# hires-Addon_Build_003.net
KiCad netlist of a schematic drawn in EAGLE
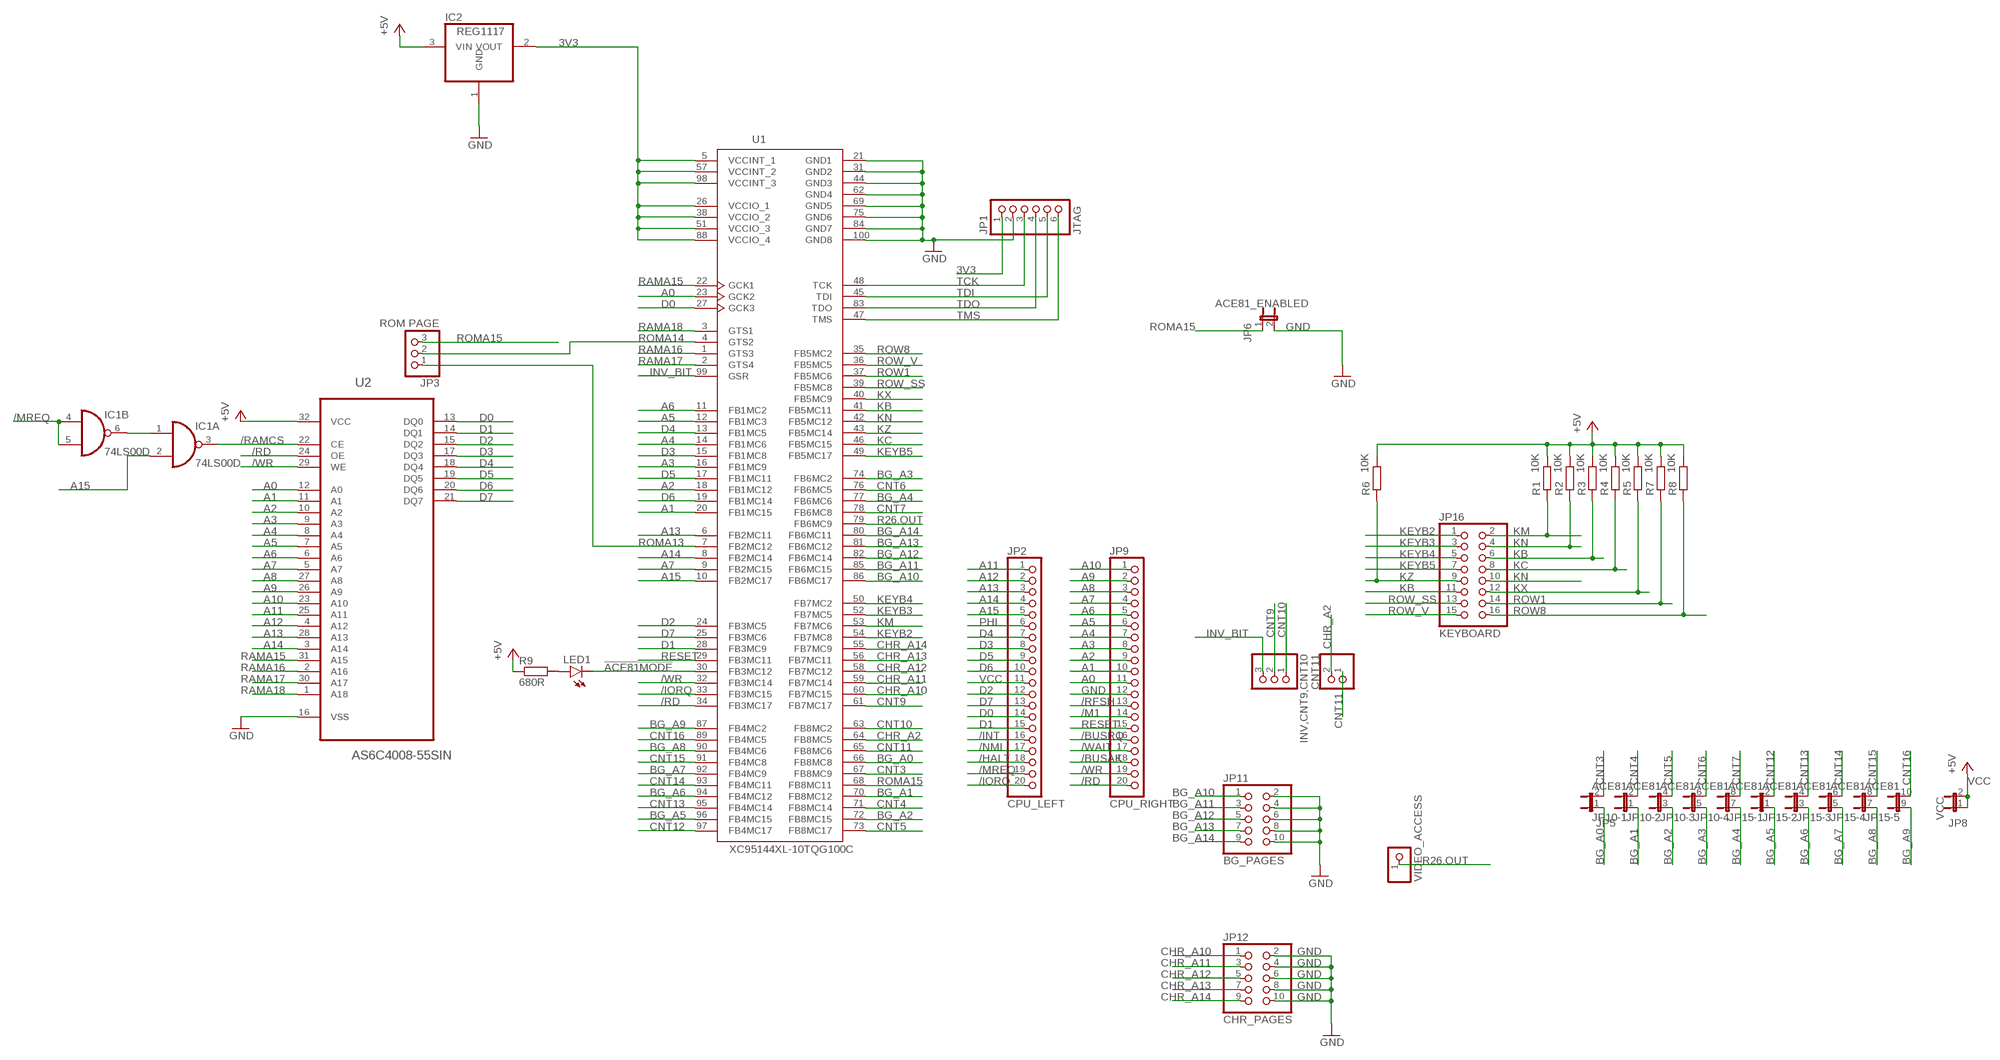
[diagram p0: schematic, sheet 1]

(export (version "E")
  (design (tool "Eeschema 10.0.6"))
  (components
    (comp (ref "CNT11")
      (value "PINHD-1X2")
      (footprint "eagle-import:1X02")
      (libsource (lib "eagle-import") (part "PINHD-1X2"))
    )
    (comp (ref "IC1")
      (value "74LS00D")
      (footprint "eagle-import:SO14")
      (libsource (lib "eagle-import") (part "7400DLS"))
    )
    (comp (ref "IC2")
      (value "REG1117")
      (footprint "eagle-import:SOT223")
      (libsource (lib "eagle-import") (part "REG1117"))
    )
    (comp (ref "INV,CNT9,CNT10")
      (value "PINHD-1X3")
      (footprint "eagle-import:1X03")
      (libsource (lib "eagle-import") (part "pinhead_44166543_PINHD-1X3"))
    )
    (comp (ref "JP1")
      (value "JTAG")
      (footprint "eagle-import:1X06_90")
      (libsource (lib "eagle-import") (part "PINHD-1X6/90"))
    )
    (comp (ref "JP2")
      (value "CPU_LEFT")
      (footprint "eagle-import:1X20")
      (libsource (lib "eagle-import") (part "PINHD-1X20"))
    )
    (comp (ref "JP3")
      (value "ROM PAGE")
      (footprint "eagle-import:1X03")
      (libsource (lib "eagle-import") (part "PINHD-1X3"))
    )
    (comp (ref "JP5")
      (value "JP1E1Q")
      (footprint "eagle-import:JP1Q")
      (libsource (lib "eagle-import") (part "JP1E1Q"))
    )
    (comp (ref "JP6")
      (value "ACE81_ENABLED")
      (footprint "eagle-import:JP1Q")
      (libsource (lib "eagle-import") (part "JP1E1Q"))
    )
    (comp (ref "JP8")
      (value "VCC")
      (footprint "eagle-import:JP1Q")
      (libsource (lib "eagle-import") (part "JP1E1Q"))
    )
    (comp (ref "JP9")
      (value "CPU_RIGHT")
      (footprint "eagle-import:1X20")
      (libsource (lib "eagle-import") (part "PINHD-1X20"))
    )
    (comp (ref "JP10")
      (value "ACE81")
      (footprint "eagle-import:JP4Q")
      (libsource (lib "eagle-import") (part "JP4QE"))
    )
    (comp (ref "JP11")
      (value "BG_PAGES")
      (footprint "eagle-import:2X05")
      (libsource (lib "eagle-import") (part "PINHD-2X5"))
    )
    (comp (ref "JP12")
      (value "CHR_PAGES")
      (footprint "eagle-import:2X05")
      (libsource (lib "eagle-import") (part "PINHD-2X5"))
    )
    (comp (ref "JP14")
      (value "VIDEO_ACCESS")
      (footprint "eagle-import:1X01")
      (libsource (lib "eagle-import") (part "PINHD-1X1"))
    )
    (comp (ref "JP15")
      (value "ACE81")
      (footprint "eagle-import:JP5Q")
      (libsource (lib "eagle-import") (part "JP5QE"))
    )
    (comp (ref "JP16")
      (value "KEYBOARD")
      (footprint "eagle-import:2X08")
      (libsource (lib "eagle-import") (part "PINHD-2X8"))
    )
    (comp (ref "LED1")
      (value "LED3MM")
      (footprint "eagle-import:LED3MM")
      (libsource (lib "eagle-import") (part "LED3MM"))
    )
    (comp (ref "R1")
      (value "10K")
      (footprint "eagle-import:0204_7")
      (libsource (lib "eagle-import") (part "R-EU_0204/7"))
    )
    (comp (ref "R2")
      (value "10K")
      (footprint "eagle-import:0204_7")
      (libsource (lib "eagle-import") (part "R-EU_0204/7"))
    )
    (comp (ref "R3")
      (value "10K")
      (footprint "eagle-import:0204_7")
      (libsource (lib "eagle-import") (part "R-EU_0204/7"))
    )
    (comp (ref "R4")
      (value "10K")
      (footprint "eagle-import:0204_7")
      (libsource (lib "eagle-import") (part "R-EU_0204/7"))
    )
    (comp (ref "R5")
      (value "10K")
      (footprint "eagle-import:0204_7")
      (libsource (lib "eagle-import") (part "R-EU_0204/7"))
    )
    (comp (ref "R6")
      (value "10K")
      (footprint "eagle-import:0204_7")
      (libsource (lib "eagle-import") (part "R-EU_0204/7"))
    )
    (comp (ref "R7")
      (value "10K")
      (footprint "eagle-import:0204_7")
      (libsource (lib "eagle-import") (part "R-EU_0204/7"))
    )
    (comp (ref "R8")
      (value "10K")
      (footprint "eagle-import:0204_7")
      (libsource (lib "eagle-import") (part "R-EU_0204/7"))
    )
    (comp (ref "R9")
      (value "680R")
      (footprint "eagle-import:0204_7")
      (libsource (lib "eagle-import") (part "R-EU_0204/7"))
    )
    (comp (ref "U1")
      (value "XC95144XL-10TQG100C")
      (footprint "eagle-import:TQFP100")
      (fields (field (name "MF") "Xilinx Inc."))
      (libsource (lib "eagle-import") (part "XC95144XL-10TQG100C"))
    )
    (comp (ref "U2")
      (value "AS6C4008-55SIN")
      (footprint "eagle-import:SOIC127P1407X299-32N")
      (fields (field (name "MF") "Alliance"))
      (libsource (lib "eagle-import") (part "AS6C4008-55SIN"))
    )
  )
  (nets
    (net (code "1") (name "+5V") (class "Default")
      (node (ref "IC2") (pin "3") (pinfunction "VIN_3") (pintype "input"))
      (node (ref "JP2") (pin "11") (pinfunction "11_11") (pintype "passive"))
      (node (ref "JP8") (pin "1") (pinfunction "1_1") (pintype "passive"))
      (node (ref "JP8") (pin "2") (pinfunction "2_2") (pintype "passive"))
      (node (ref "R1") (pin "2") (pinfunction "2_2") (pintype "passive"))
      (node (ref "R2") (pin "2") (pinfunction "2_2") (pintype "passive"))
      (node (ref "R3") (pin "2") (pinfunction "2_2") (pintype "passive"))
      (node (ref "R4") (pin "2") (pinfunction "2_2") (pintype "passive"))
      (node (ref "R5") (pin "2") (pinfunction "2_2") (pintype "passive"))
      (node (ref "R6") (pin "2") (pinfunction "2_2") (pintype "passive"))
      (node (ref "R7") (pin "2") (pinfunction "2_2") (pintype "passive"))
      (node (ref "R8") (pin "2") (pinfunction "2_2") (pintype "passive"))
      (node (ref "R9") (pin "1") (pinfunction "1_1") (pintype "passive"))
      (node (ref "U2") (pin "32") (pinfunction "VCC_32") (pintype "power_in"))
    )
    (net (code "2") (name "/3V3") (class "Default")
      (node (ref "IC2") (pin "2") (pinfunction "VOUT_2") (pintype "output"))
      (node (ref "JP1") (pin "1") (pinfunction "1_1") (pintype "passive"))
      (node (ref "U1") (pin "26") (pinfunction "VCCIO_1_26") (pintype "power_in"))
      (node (ref "U1") (pin "38") (pinfunction "VCCIO_2_38") (pintype "power_in"))
      (node (ref "U1") (pin "5") (pinfunction "VCCINT_1_5") (pintype "power_in"))
      (node (ref "U1") (pin "51") (pinfunction "VCCIO_3_51") (pintype "power_in"))
      (node (ref "U1") (pin "57") (pinfunction "VCCINT_2_57") (pintype "power_in"))
      (node (ref "U1") (pin "88") (pinfunction "VCCIO_4_88") (pintype "power_in"))
      (node (ref "U1") (pin "98") (pinfunction "VCCINT_3_98") (pintype "power_in"))
    )
    (net (code "3") (name "/A0") (class "Default")
      (node (ref "JP9") (pin "11") (pinfunction "11_11") (pintype "passive"))
      (node (ref "U1") (pin "23") (pinfunction "GCK2_23") (pintype "bidirectional"))
      (node (ref "U2") (pin "12") (pinfunction "A0_12") (pintype "input"))
    )
    (net (code "4") (name "/A1") (class "Default")
      (node (ref "JP9") (pin "10") (pinfunction "10_10") (pintype "passive"))
      (node (ref "U1") (pin "20") (pinfunction "FB1MC15_20") (pintype "bidirectional"))
      (node (ref "U2") (pin "11") (pinfunction "A1_11") (pintype "input"))
    )
    (net (code "5") (name "/A2") (class "Default")
      (node (ref "JP9") (pin "9") (pinfunction "9_9") (pintype "passive"))
      (node (ref "U1") (pin "18") (pinfunction "FB1MC12_18") (pintype "bidirectional"))
      (node (ref "U2") (pin "10") (pinfunction "A2_10") (pintype "input"))
    )
    (net (code "6") (name "/A3") (class "Default")
      (node (ref "JP9") (pin "8") (pinfunction "8_8") (pintype "passive"))
      (node (ref "U1") (pin "16") (pinfunction "FB1MC9_16") (pintype "bidirectional"))
      (node (ref "U2") (pin "9") (pinfunction "A3_9") (pintype "input"))
    )
    (net (code "7") (name "/A4") (class "Default")
      (node (ref "JP9") (pin "7") (pinfunction "7_7") (pintype "passive"))
      (node (ref "U1") (pin "14") (pinfunction "FB1MC6_14") (pintype "bidirectional"))
      (node (ref "U2") (pin "8") (pinfunction "A4_8") (pintype "input"))
    )
    (net (code "8") (name "/A5") (class "Default")
      (node (ref "JP9") (pin "6") (pinfunction "6_6") (pintype "passive"))
      (node (ref "U1") (pin "12") (pinfunction "FB1MC3_12") (pintype "bidirectional"))
      (node (ref "U2") (pin "7") (pinfunction "A5_7") (pintype "input"))
    )
    (net (code "9") (name "/A6") (class "Default")
      (node (ref "JP9") (pin "5") (pinfunction "5_5") (pintype "passive"))
      (node (ref "U1") (pin "11") (pinfunction "FB1MC2_11") (pintype "bidirectional"))
      (node (ref "U2") (pin "6") (pinfunction "A6_6") (pintype "input"))
    )
    (net (code "10") (name "/A7") (class "Default")
      (node (ref "JP9") (pin "4") (pinfunction "4_4") (pintype "passive"))
      (node (ref "U1") (pin "9") (pinfunction "FB2MC15_9") (pintype "bidirectional"))
      (node (ref "U2") (pin "5") (pinfunction "A7_5") (pintype "input"))
    )
    (net (code "11") (name "/A8") (class "Default")
      (node (ref "JP9") (pin "3") (pinfunction "3_3") (pintype "passive"))
      (node (ref "U2") (pin "27") (pinfunction "A8_27") (pintype "input"))
    )
    (net (code "12") (name "/A9") (class "Default")
      (node (ref "JP9") (pin "2") (pinfunction "2_2") (pintype "passive"))
      (node (ref "U2") (pin "26") (pinfunction "A9_26") (pintype "input"))
    )
    (net (code "13") (name "/A10") (class "Default")
      (node (ref "JP9") (pin "1") (pinfunction "1_1") (pintype "passive"))
      (node (ref "U2") (pin "23") (pinfunction "A10_23") (pintype "input"))
    )
    (net (code "14") (name "/A11") (class "Default")
      (node (ref "JP2") (pin "1") (pinfunction "1_1") (pintype "passive"))
      (node (ref "U2") (pin "25") (pinfunction "A11_25") (pintype "input"))
    )
    (net (code "15") (name "/A12") (class "Default")
      (node (ref "JP2") (pin "2") (pinfunction "2_2") (pintype "passive"))
      (node (ref "U2") (pin "4") (pinfunction "A12_4") (pintype "input"))
    )
    (net (code "16") (name "/A13") (class "Default")
      (node (ref "JP2") (pin "3") (pinfunction "3_3") (pintype "passive"))
      (node (ref "U1") (pin "6") (pinfunction "FB2MC11_6") (pintype "bidirectional"))
      (node (ref "U2") (pin "28") (pinfunction "A13_28") (pintype "input"))
    )
    (net (code "17") (name "/A14") (class "Default")
      (node (ref "JP2") (pin "4") (pinfunction "4_4") (pintype "passive"))
      (node (ref "U1") (pin "8") (pinfunction "FB2MC14_8") (pintype "bidirectional"))
      (node (ref "U2") (pin "3") (pinfunction "A14_3") (pintype "input"))
    )
    (net (code "18") (name "/A15") (class "Default")
      (node (ref "IC1") (pin "2") (pinfunction "I1_2") (pintype "input"))
      (node (ref "JP2") (pin "5") (pinfunction "5_5") (pintype "passive"))
      (node (ref "U1") (pin "10") (pinfunction "FB2MC17_10") (pintype "bidirectional"))
    )
    (net (code "19") (name "/BG_A0") (class "Default")
      (node (ref "JP5") (pin "1") (pinfunction "1_1") (pintype "passive"))
      (node (ref "U1") (pin "66") (pinfunction "FB8MC8_66") (pintype "bidirectional"))
    )
    (net (code "20") (name "/BG_A1") (class "Default")
      (node (ref "JP10") (pin "1") (pinfunction "1_1") (pintype "passive"))
      (node (ref "U1") (pin "70") (pinfunction "FB8MC12_70") (pintype "bidirectional"))
    )
    (net (code "21") (name "/BG_A2") (class "Default")
      (node (ref "JP10") (pin "3") (pinfunction "1_3") (pintype "passive"))
      (node (ref "U1") (pin "72") (pinfunction "FB8MC15_72") (pintype "bidirectional"))
    )
    (net (code "22") (name "/BG_A3") (class "Default")
      (node (ref "JP10") (pin "5") (pinfunction "1_5") (pintype "passive"))
      (node (ref "U1") (pin "74") (pinfunction "FB6MC2_74") (pintype "bidirectional"))
    )
    (net (code "23") (name "/BG_A4") (class "Default")
      (node (ref "JP10") (pin "7") (pinfunction "1_7") (pintype "passive"))
      (node (ref "U1") (pin "77") (pinfunction "FB6MC6_77") (pintype "bidirectional"))
    )
    (net (code "24") (name "/BG_A5") (class "Default")
      (node (ref "JP15") (pin "1") (pinfunction "1_1") (pintype "passive"))
      (node (ref "U1") (pin "96") (pinfunction "FB4MC15_96") (pintype "bidirectional"))
    )
    (net (code "25") (name "/BG_A6") (class "Default")
      (node (ref "JP15") (pin "3") (pinfunction "1_3") (pintype "passive"))
      (node (ref "U1") (pin "94") (pinfunction "FB4MC12_94") (pintype "bidirectional"))
    )
    (net (code "26") (name "/BG_A7") (class "Default")
      (node (ref "JP15") (pin "5") (pinfunction "1_5") (pintype "passive"))
      (node (ref "U1") (pin "92") (pinfunction "FB4MC9_92") (pintype "bidirectional"))
    )
    (net (code "27") (name "/BG_A8") (class "Default")
      (node (ref "JP15") (pin "7") (pinfunction "1_7") (pintype "passive"))
      (node (ref "U1") (pin "90") (pinfunction "FB4MC6_90") (pintype "bidirectional"))
    )
    (net (code "28") (name "/BG_A9") (class "Default")
      (node (ref "JP15") (pin "9") (pinfunction "1_9") (pintype "passive"))
      (node (ref "U1") (pin "87") (pinfunction "FB4MC2_87") (pintype "bidirectional"))
    )
    (net (code "29") (name "/BG_A10") (class "Default")
      (node (ref "JP11") (pin "1") (pinfunction "1_1") (pintype "passive"))
      (node (ref "U1") (pin "86") (pinfunction "FB6MC17_86") (pintype "bidirectional"))
    )
    (net (code "30") (name "/BG_A11") (class "Default")
      (node (ref "JP11") (pin "3") (pinfunction "3_3") (pintype "passive"))
      (node (ref "U1") (pin "85") (pinfunction "FB6MC15_85") (pintype "bidirectional"))
    )
    (net (code "31") (name "/BG_A12") (class "Default")
      (node (ref "JP11") (pin "5") (pinfunction "5_5") (pintype "passive"))
      (node (ref "U1") (pin "82") (pinfunction "FB6MC14_82") (pintype "bidirectional"))
    )
    (net (code "32") (name "/BG_A13") (class "Default")
      (node (ref "JP11") (pin "7") (pinfunction "7_7") (pintype "passive"))
      (node (ref "U1") (pin "81") (pinfunction "FB6MC12_81") (pintype "bidirectional"))
    )
    (net (code "33") (name "/BG_A14") (class "Default")
      (node (ref "JP11") (pin "9") (pinfunction "9_9") (pintype "passive"))
      (node (ref "U1") (pin "80") (pinfunction "FB6MC11_80") (pintype "bidirectional"))
    )
    (net (code "34") (name "/CHR_A2") (class "Default")
      (node (ref "CNT11") (pin "2") (pinfunction "2_2") (pintype "passive"))
      (node (ref "U1") (pin "64") (pinfunction "FB8MC5_64") (pintype "bidirectional"))
    )
    (net (code "35") (name "/CHR_A10") (class "Default")
      (node (ref "JP12") (pin "1") (pinfunction "1_1") (pintype "passive"))
      (node (ref "U1") (pin "60") (pinfunction "FB7MC15_60") (pintype "bidirectional"))
    )
    (net (code "36") (name "/CHR_A11") (class "Default")
      (node (ref "JP12") (pin "3") (pinfunction "3_3") (pintype "passive"))
      (node (ref "U1") (pin "59") (pinfunction "FB7MC14_59") (pintype "bidirectional"))
    )
    (net (code "37") (name "/CHR_A12") (class "Default")
      (node (ref "JP12") (pin "5") (pinfunction "5_5") (pintype "passive"))
      (node (ref "U1") (pin "58") (pinfunction "FB7MC12_58") (pintype "bidirectional"))
    )
    (net (code "38") (name "/CHR_A13") (class "Default")
      (node (ref "JP12") (pin "7") (pinfunction "7_7") (pintype "passive"))
      (node (ref "U1") (pin "56") (pinfunction "FB7MC11_56") (pintype "bidirectional"))
    )
    (net (code "39") (name "/CHR_A14") (class "Default")
      (node (ref "JP12") (pin "9") (pinfunction "9_9") (pintype "passive"))
      (node (ref "U1") (pin "55") (pinfunction "FB7MC9_55") (pintype "bidirectional"))
    )
    (net (code "40") (name "/CNT3") (class "Default")
      (node (ref "JP5") (pin "2") (pinfunction "2_2") (pintype "passive"))
      (node (ref "U1") (pin "67") (pinfunction "FB8MC9_67") (pintype "bidirectional"))
    )
    (net (code "41") (name "/CNT4") (class "Default")
      (node (ref "JP10") (pin "2") (pinfunction "2_2") (pintype "passive"))
      (node (ref "U1") (pin "71") (pinfunction "FB8MC14_71") (pintype "bidirectional"))
    )
    (net (code "42") (name "/CNT5") (class "Default")
      (node (ref "JP10") (pin "4") (pinfunction "2_4") (pintype "passive"))
      (node (ref "U1") (pin "73") (pinfunction "FB8MC17_73") (pintype "bidirectional"))
    )
    (net (code "43") (name "/CNT6") (class "Default")
      (node (ref "JP10") (pin "6") (pinfunction "2_6") (pintype "passive"))
      (node (ref "U1") (pin "76") (pinfunction "FB6MC5_76") (pintype "bidirectional"))
    )
    (net (code "44") (name "/CNT7") (class "Default")
      (node (ref "JP10") (pin "8") (pinfunction "2_8") (pintype "passive"))
      (node (ref "U1") (pin "78") (pinfunction "FB6MC8_78") (pintype "bidirectional"))
    )
    (net (code "45") (name "/CNT9") (class "Default")
      (node (ref "INV,CNT9,CNT10") (pin "2") (pinfunction "2_2") (pintype "passive"))
      (node (ref "U1") (pin "61") (pinfunction "FB7MC17_61") (pintype "bidirectional"))
    )
    (net (code "46") (name "/CNT10") (class "Default")
      (node (ref "INV,CNT9,CNT10") (pin "1") (pinfunction "1_1") (pintype "passive"))
      (node (ref "U1") (pin "63") (pinfunction "FB8MC2_63") (pintype "bidirectional"))
    )
    (net (code "47") (name "/CNT11") (class "Default")
      (node (ref "CNT11") (pin "1") (pinfunction "1_1") (pintype "passive"))
      (node (ref "U1") (pin "65") (pinfunction "FB8MC6_65") (pintype "bidirectional"))
    )
    (net (code "48") (name "/CNT12") (class "Default")
      (node (ref "JP15") (pin "2") (pinfunction "2_2") (pintype "passive"))
      (node (ref "U1") (pin "97") (pinfunction "FB4MC17_97") (pintype "bidirectional"))
    )
    (net (code "49") (name "/CNT13") (class "Default")
      (node (ref "JP15") (pin "4") (pinfunction "2_4") (pintype "passive"))
      (node (ref "U1") (pin "95") (pinfunction "FB4MC14_95") (pintype "bidirectional"))
    )
    (net (code "50") (name "/CNT14") (class "Default")
      (node (ref "JP15") (pin "6") (pinfunction "2_6") (pintype "passive"))
      (node (ref "U1") (pin "93") (pinfunction "FB4MC11_93") (pintype "bidirectional"))
    )
    (net (code "51") (name "/CNT15") (class "Default")
      (node (ref "JP15") (pin "8") (pinfunction "2_8") (pintype "passive"))
      (node (ref "U1") (pin "91") (pinfunction "FB4MC8_91") (pintype "bidirectional"))
    )
    (net (code "52") (name "/CNT16") (class "Default")
      (node (ref "JP15") (pin "10") (pinfunction "2_10") (pintype "passive"))
      (node (ref "U1") (pin "89") (pinfunction "FB4MC5_89") (pintype "bidirectional"))
    )
    (net (code "53") (name "/D0") (class "Default")
      (node (ref "JP2") (pin "14") (pinfunction "14_14") (pintype "passive"))
      (node (ref "U1") (pin "27") (pinfunction "GCK3_27") (pintype "bidirectional"))
      (node (ref "U2") (pin "13") (pinfunction "DQ0_13") (pintype "output"))
    )
    (net (code "54") (name "/D1") (class "Default")
      (node (ref "JP2") (pin "15") (pinfunction "15_15") (pintype "passive"))
      (node (ref "U1") (pin "28") (pinfunction "FB3MC9_28") (pintype "bidirectional"))
      (node (ref "U2") (pin "14") (pinfunction "DQ1_14") (pintype "output"))
    )
    (net (code "55") (name "/D2") (class "Default")
      (node (ref "JP2") (pin "12") (pinfunction "12_12") (pintype "passive"))
      (node (ref "U1") (pin "24") (pinfunction "FB3MC5_24") (pintype "bidirectional"))
      (node (ref "U2") (pin "15") (pinfunction "DQ2_15") (pintype "output"))
    )
    (net (code "56") (name "/D3") (class "Default")
      (node (ref "JP2") (pin "8") (pinfunction "8_8") (pintype "passive"))
      (node (ref "U1") (pin "15") (pinfunction "FB1MC8_15") (pintype "bidirectional"))
      (node (ref "U2") (pin "17") (pinfunction "DQ3_17") (pintype "output"))
    )
    (net (code "57") (name "/D4") (class "Default")
      (node (ref "JP2") (pin "7") (pinfunction "7_7") (pintype "passive"))
      (node (ref "U1") (pin "13") (pinfunction "FB1MC5_13") (pintype "bidirectional"))
      (node (ref "U2") (pin "18") (pinfunction "DQ4_18") (pintype "output"))
    )
    (net (code "58") (name "/D5") (class "Default")
      (node (ref "JP2") (pin "9") (pinfunction "9_9") (pintype "passive"))
      (node (ref "U1") (pin "17") (pinfunction "FB1MC11_17") (pintype "bidirectional"))
      (node (ref "U2") (pin "19") (pinfunction "DQ5_19") (pintype "output"))
    )
    (net (code "59") (name "/D6") (class "Default")
      (node (ref "JP2") (pin "10") (pinfunction "10_10") (pintype "passive"))
      (node (ref "U1") (pin "19") (pinfunction "FB1MC14_19") (pintype "bidirectional"))
      (node (ref "U2") (pin "20") (pinfunction "DQ6_20") (pintype "output"))
    )
    (net (code "60") (name "/D7") (class "Default")
      (node (ref "JP2") (pin "13") (pinfunction "13_13") (pintype "passive"))
      (node (ref "U1") (pin "25") (pinfunction "FB3MC6_25") (pintype "bidirectional"))
      (node (ref "U2") (pin "21") (pinfunction "DQ7_21") (pintype "output"))
    )
    (net (code "61") (name "/INV_BIT") (class "Default")
      (node (ref "INV,CNT9,CNT10") (pin "3") (pinfunction "3_3") (pintype "passive"))
      (node (ref "U1") (pin "99") (pinfunction "GSR_99") (pintype "bidirectional"))
    )
    (net (code "62") (name "/KB") (class "Default")
      (node (ref "JP16") (pin "11") (pinfunction "11_11") (pintype "passive"))
      (node (ref "JP16") (pin "6") (pinfunction "6_6") (pintype "passive"))
      (node (ref "R3") (pin "1") (pinfunction "1_1") (pintype "passive"))
      (node (ref "U1") (pin "41") (pinfunction "FB5MC11_41") (pintype "bidirectional"))
    )
    (net (code "63") (name "/KC") (class "Default")
      (node (ref "JP16") (pin "8") (pinfunction "8_8") (pintype "passive"))
      (node (ref "R4") (pin "1") (pinfunction "1_1") (pintype "passive"))
      (node (ref "U1") (pin "46") (pinfunction "FB5MC15_46") (pintype "bidirectional"))
    )
    (net (code "64") (name "/KEYB2") (class "Default")
      (node (ref "JP16") (pin "1") (pinfunction "1_1") (pintype "passive"))
      (node (ref "U1") (pin "54") (pinfunction "FB7MC8_54") (pintype "bidirectional"))
    )
    (net (code "65") (name "/KEYB3") (class "Default")
      (node (ref "JP16") (pin "3") (pinfunction "3_3") (pintype "passive"))
      (node (ref "U1") (pin "52") (pinfunction "FB7MC5_52") (pintype "bidirectional"))
    )
    (net (code "66") (name "/KEYB4") (class "Default")
      (node (ref "JP16") (pin "5") (pinfunction "5_5") (pintype "passive"))
      (node (ref "U1") (pin "50") (pinfunction "FB7MC2_50") (pintype "bidirectional"))
    )
    (net (code "67") (name "/KEYB5") (class "Default")
      (node (ref "JP16") (pin "7") (pinfunction "7_7") (pintype "passive"))
      (node (ref "U1") (pin "49") (pinfunction "FB5MC17_49") (pintype "bidirectional"))
    )
    (net (code "68") (name "/KM") (class "Default")
      (node (ref "JP16") (pin "2") (pinfunction "2_2") (pintype "passive"))
      (node (ref "R1") (pin "1") (pinfunction "1_1") (pintype "passive"))
      (node (ref "U1") (pin "53") (pinfunction "FB7MC6_53") (pintype "bidirectional"))
    )
    (net (code "69") (name "/KN") (class "Default")
      (node (ref "JP16") (pin "10") (pinfunction "10_10") (pintype "passive"))
      (node (ref "JP16") (pin "4") (pinfunction "4_4") (pintype "passive"))
      (node (ref "R2") (pin "1") (pinfunction "1_1") (pintype "passive"))
      (node (ref "U1") (pin "42") (pinfunction "FB5MC12_42") (pintype "bidirectional"))
    )
    (net (code "70") (name "/KX") (class "Default")
      (node (ref "JP16") (pin "12") (pinfunction "12_12") (pintype "passive"))
      (node (ref "R5") (pin "1") (pinfunction "1_1") (pintype "passive"))
      (node (ref "U1") (pin "40") (pinfunction "FB5MC9_40") (pintype "bidirectional"))
    )
    (net (code "71") (name "/KZ") (class "Default")
      (node (ref "JP16") (pin "9") (pinfunction "9_9") (pintype "passive"))
      (node (ref "R6") (pin "1") (pinfunction "1_1") (pintype "passive"))
      (node (ref "U1") (pin "43") (pinfunction "FB5MC14_43") (pintype "bidirectional"))
    )
    (net (code "72") (name "/PHI") (class "Default")
      (node (ref "JP2") (pin "6") (pinfunction "6_6") (pintype "passive"))
    )
    (net (code "73") (name "/R26.OUT") (class "Default")
      (node (ref "JP14") (pin "1") (pinfunction "1_1") (pintype "passive"))
      (node (ref "U1") (pin "79") (pinfunction "FB6MC9_79") (pintype "bidirectional"))
    )
    (net (code "74") (name "/RAMA15") (class "Default")
      (node (ref "U1") (pin "22") (pinfunction "GCK1_22") (pintype "bidirectional"))
      (node (ref "U2") (pin "31") (pinfunction "A15_31") (pintype "input"))
    )
    (net (code "75") (name "/RAMA16") (class "Default")
      (node (ref "U1") (pin "1") (pinfunction "GTS3_1") (pintype "bidirectional"))
      (node (ref "U2") (pin "2") (pinfunction "A16_2") (pintype "input"))
    )
    (net (code "76") (name "/RAMA17") (class "Default")
      (node (ref "U1") (pin "2") (pinfunction "GTS4_2") (pintype "bidirectional"))
      (node (ref "U2") (pin "30") (pinfunction "A17_30") (pintype "input"))
    )
    (net (code "77") (name "/RAMA18") (class "Default")
      (node (ref "U1") (pin "3") (pinfunction "GTS1_3") (pintype "bidirectional"))
      (node (ref "U2") (pin "1") (pinfunction "A18_1") (pintype "input"))
    )
    (net (code "78") (name "/RESET") (class "Default")
      (node (ref "JP9") (pin "15") (pinfunction "15_15") (pintype "passive"))
      (node (ref "U1") (pin "29") (pinfunction "FB3MC11_29") (pintype "bidirectional"))
    )
    (net (code "79") (name "/ROMA13") (class "Default")
      (node (ref "JP3") (pin "1") (pinfunction "1_1") (pintype "passive"))
      (node (ref "U1") (pin "7") (pinfunction "FB2MC12_7") (pintype "bidirectional"))
    )
    (net (code "80") (name "/ROMA14") (class "Default")
      (node (ref "JP3") (pin "2") (pinfunction "2_2") (pintype "passive"))
      (node (ref "U1") (pin "4") (pinfunction "GTS2_4") (pintype "bidirectional"))
    )
    (net (code "81") (name "/ROMA15") (class "Default")
      (node (ref "JP3") (pin "3") (pinfunction "3_3") (pintype "passive"))
      (node (ref "JP6") (pin "1") (pinfunction "1_1") (pintype "passive"))
      (node (ref "U1") (pin "68") (pinfunction "FB8MC11_68") (pintype "bidirectional"))
    )
    (net (code "82") (name "/ROW1") (class "Default")
      (node (ref "JP16") (pin "14") (pinfunction "14_14") (pintype "passive"))
      (node (ref "R7") (pin "1") (pinfunction "1_1") (pintype "passive"))
      (node (ref "U1") (pin "37") (pinfunction "FB5MC6_37") (pintype "bidirectional"))
    )
    (net (code "83") (name "/ROW8") (class "Default")
      (node (ref "JP16") (pin "16") (pinfunction "16_16") (pintype "passive"))
      (node (ref "R8") (pin "1") (pinfunction "1_1") (pintype "passive"))
      (node (ref "U1") (pin "35") (pinfunction "FB5MC2_35") (pintype "bidirectional"))
    )
    (net (code "84") (name "/ROW_SS") (class "Default")
      (node (ref "JP16") (pin "13") (pinfunction "13_13") (pintype "passive"))
      (node (ref "U1") (pin "39") (pinfunction "FB5MC8_39") (pintype "bidirectional"))
    )
    (net (code "85") (name "/ROW_V") (class "Default")
      (node (ref "JP16") (pin "15") (pinfunction "15_15") (pintype "passive"))
      (node (ref "U1") (pin "36") (pinfunction "FB5MC5_36") (pintype "bidirectional"))
    )
    (net (code "86") (name "/TCK") (class "Default")
      (node (ref "JP1") (pin "3") (pinfunction "3_3") (pintype "passive"))
      (node (ref "U1") (pin "48") (pinfunction "TCK_48") (pintype "passive"))
    )
    (net (code "87") (name "/TDI") (class "Default")
      (node (ref "JP1") (pin "5") (pinfunction "5_5") (pintype "passive"))
      (node (ref "U1") (pin "45") (pinfunction "TDI_45") (pintype "passive"))
    )
    (net (code "88") (name "/TDO") (class "Default")
      (node (ref "JP1") (pin "4") (pinfunction "4_4") (pintype "passive"))
      (node (ref "U1") (pin "83") (pinfunction "TDO_83") (pintype "passive"))
    )
    (net (code "89") (name "/TMS") (class "Default")
      (node (ref "JP1") (pin "6") (pinfunction "6_6") (pintype "passive"))
      (node (ref "U1") (pin "47") (pinfunction "TMS_47") (pintype "passive"))
    )
    (net (code "90") (name "/{slash}BUSAK") (class "Default")
      (node (ref "JP9") (pin "18") (pinfunction "18_18") (pintype "passive"))
    )
    (net (code "91") (name "/{slash}BUSRQ") (class "Default")
      (node (ref "JP9") (pin "16") (pinfunction "16_16") (pintype "passive"))
    )
    (net (code "92") (name "/{slash}HALT") (class "Default")
      (node (ref "JP2") (pin "18") (pinfunction "18_18") (pintype "passive"))
    )
    (net (code "93") (name "/{slash}INT") (class "Default")
      (node (ref "JP2") (pin "16") (pinfunction "16_16") (pintype "passive"))
    )
    (net (code "94") (name "/{slash}IORQ") (class "Default")
      (node (ref "JP2") (pin "20") (pinfunction "20_20") (pintype "passive"))
      (node (ref "U1") (pin "33") (pinfunction "FB3MC15_33") (pintype "bidirectional"))
    )
    (net (code "95") (name "/{slash}M1") (class "Default")
      (node (ref "JP9") (pin "14") (pinfunction "14_14") (pintype "passive"))
    )
    (net (code "96") (name "/{slash}MREQ") (class "Default")
      (node (ref "IC1") (pin "4") (pinfunction "I0_4") (pintype "input"))
      (node (ref "IC1") (pin "5") (pinfunction "I1_5") (pintype "input"))
      (node (ref "JP2") (pin "19") (pinfunction "19_19") (pintype "passive"))
    )
    (net (code "97") (name "/{slash}NMI") (class "Default")
      (node (ref "JP2") (pin "17") (pinfunction "17_17") (pintype "passive"))
    )
    (net (code "98") (name "/{slash}RAMCS") (class "Default")
      (node (ref "IC1") (pin "3") (pinfunction "O_3") (pintype "output"))
      (node (ref "U2") (pin "22") (pinfunction "CE_22") (pintype "input"))
    )
    (net (code "99") (name "/{slash}RD") (class "Default")
      (node (ref "JP9") (pin "20") (pinfunction "20_20") (pintype "passive"))
      (node (ref "U1") (pin "34") (pinfunction "FB3MC17_34") (pintype "bidirectional"))
      (node (ref "U2") (pin "24") (pinfunction "OE_24") (pintype "input"))
    )
    (net (code "100") (name "/{slash}RFSH") (class "Default")
      (node (ref "JP9") (pin "13") (pinfunction "13_13") (pintype "passive"))
    )
    (net (code "101") (name "/{slash}WAIT") (class "Default")
      (node (ref "JP9") (pin "17") (pinfunction "17_17") (pintype "passive"))
    )
    (net (code "102") (name "/{slash}WR") (class "Default")
      (node (ref "JP9") (pin "19") (pinfunction "19_19") (pintype "passive"))
      (node (ref "U1") (pin "32") (pinfunction "FB3MC14_32") (pintype "bidirectional"))
      (node (ref "U2") (pin "29") (pinfunction "WE_29") (pintype "input"))
    )
    (net (code "103") (name "/~{ACE81MODE}") (class "Default")
      (node (ref "LED1") (pin "K") (pinfunction "C_K") (pintype "passive"))
      (node (ref "U1") (pin "30") (pinfunction "FB3MC12_30") (pintype "bidirectional"))
    )
    (net (code "104") (name "GND") (class "Default")
      (node (ref "IC2") (pin "1") (pinfunction "GND_1") (pintype "power_in"))
      (node (ref "JP1") (pin "2") (pinfunction "2_2") (pintype "passive"))
      (node (ref "JP11") (pin "10") (pinfunction "10_10") (pintype "passive"))
      (node (ref "JP11") (pin "2") (pinfunction "2_2") (pintype "passive"))
      (node (ref "JP11") (pin "4") (pinfunction "4_4") (pintype "passive"))
      (node (ref "JP11") (pin "6") (pinfunction "6_6") (pintype "passive"))
      (node (ref "JP11") (pin "8") (pinfunction "8_8") (pintype "passive"))
      (node (ref "JP12") (pin "10") (pinfunction "10_10") (pintype "passive"))
      (node (ref "JP12") (pin "2") (pinfunction "2_2") (pintype "passive"))
      (node (ref "JP12") (pin "4") (pinfunction "4_4") (pintype "passive"))
      (node (ref "JP12") (pin "6") (pinfunction "6_6") (pintype "passive"))
      (node (ref "JP12") (pin "8") (pinfunction "8_8") (pintype "passive"))
      (node (ref "JP6") (pin "2") (pinfunction "2_2") (pintype "passive"))
      (node (ref "JP9") (pin "12") (pinfunction "12_12") (pintype "passive"))
      (node (ref "U1") (pin "100") (pinfunction "GND8_100") (pintype "power_in"))
      (node (ref "U1") (pin "21") (pinfunction "GND1_21") (pintype "power_in"))
      (node (ref "U1") (pin "31") (pinfunction "GND2_31") (pintype "power_in"))
      (node (ref "U1") (pin "44") (pinfunction "GND3_44") (pintype "power_in"))
      (node (ref "U1") (pin "62") (pinfunction "GND4_62") (pintype "power_in"))
      (node (ref "U1") (pin "69") (pinfunction "GND5_69") (pintype "power_in"))
      (node (ref "U1") (pin "75") (pinfunction "GND6_75") (pintype "power_in"))
      (node (ref "U1") (pin "84") (pinfunction "GND7_84") (pintype "power_in"))
      (node (ref "U2") (pin "16") (pinfunction "VSS_16") (pintype "output"))
    )
    (net (code "105") (name "Net-(IC1A-I0)") (class "Default")
      (node (ref "IC1") (pin "1") (pinfunction "I0_1") (pintype "input"))
      (node (ref "IC1") (pin "6") (pinfunction "O_6") (pintype "output"))
    )
    (net (code "106") (name "Net-(LED1-PadA)") (class "Default")
      (node (ref "LED1") (pin "A") (pinfunction "A_A") (pintype "passive"))
      (node (ref "R9") (pin "2") (pinfunction "2_2") (pintype "passive"))
    )
  )
)
